# SalidasDigitales.net
KiCad netlist of a schematic drawn in Altium Designer
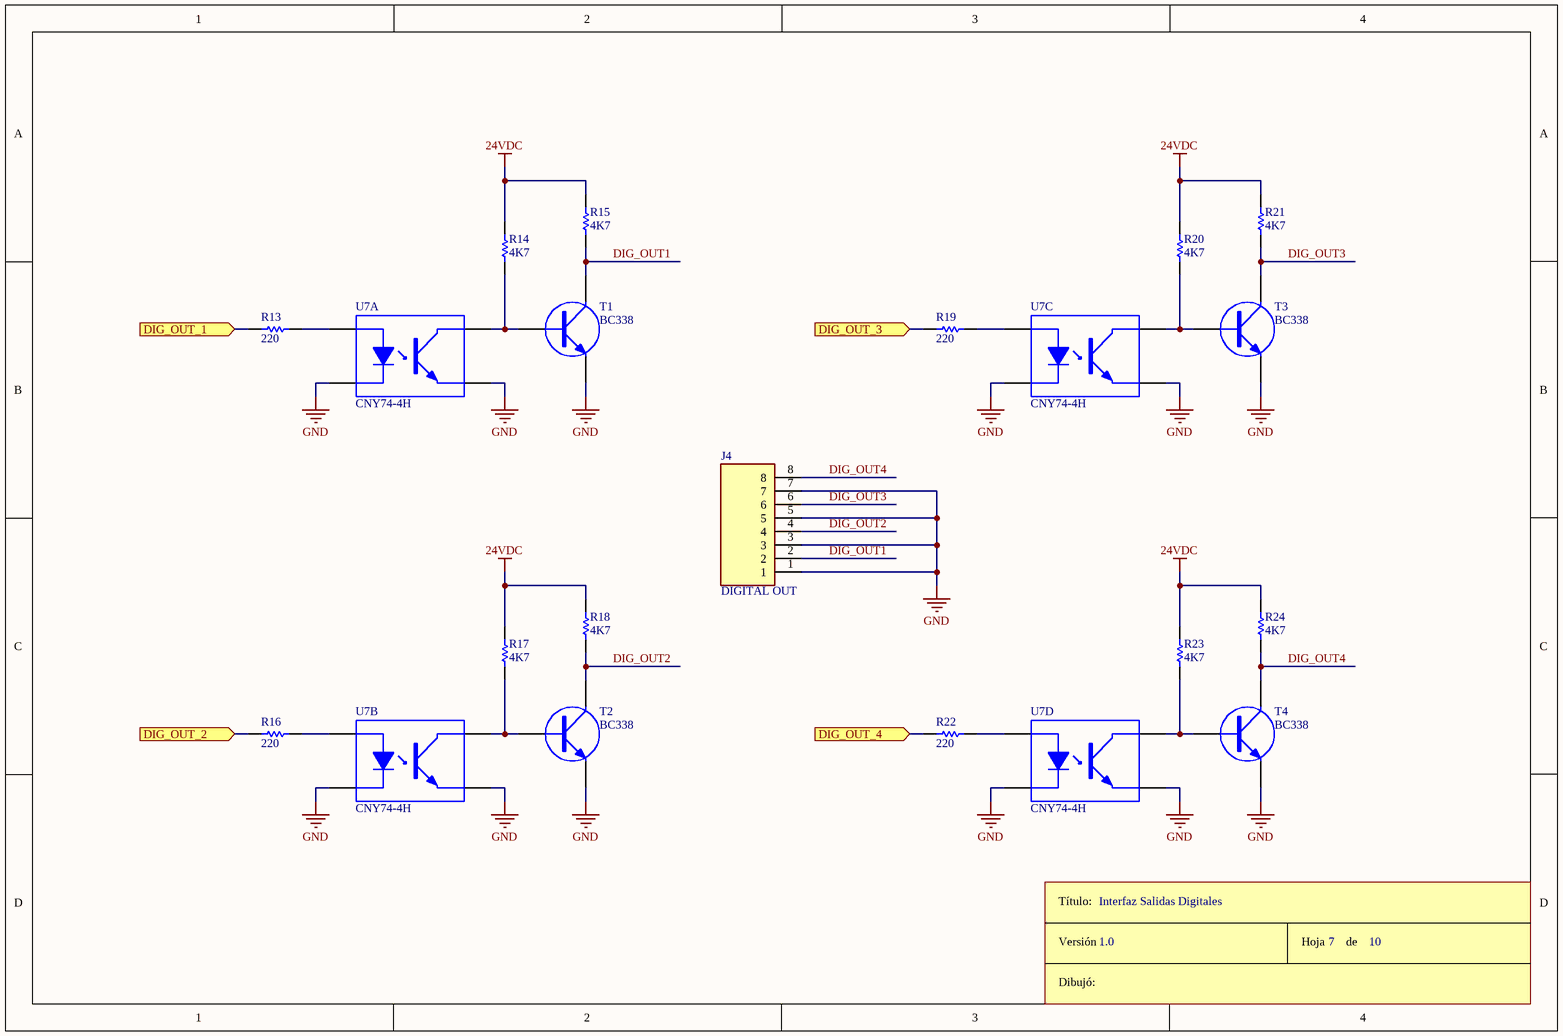
[diagram p0: SalidasDigitales.SchDoc]

(export (version "E")
  (design (tool "Eeschema 10.0.6"))
  (components
    (comp (ref "J4")
      (value "DIGITAL OUT")
      (footprint "TE_1586863-8")
      (description "Conn Power HDR 8 POS 4.2mm Solder RA Thru-Hole 8 Terminal 1 Port Tray")
      (fields (field (name "MF") "TE Connectivity") (field (name "MP") "1586863-8"))
      (libsource (lib "MFW8R") (part "1586863-8"))
    )
    (comp (ref "R13") (value "220") (footprint "RES300") (libsource (lib "LIBEBAL") (part "RES")))
    (comp (ref "R14") (value "4K7") (footprint "RES400") (libsource (lib "LIBEBAL") (part "RES")))
    (comp (ref "R15") (value "4K7") (footprint "RES400") (libsource (lib "LIBEBAL") (part "RES")))
    (comp (ref "R16") (value "220") (footprint "RES300") (libsource (lib "LIBEBAL") (part "RES")))
    (comp (ref "R17") (value "4K7") (footprint "RES400") (libsource (lib "LIBEBAL") (part "RES")))
    (comp (ref "R18") (value "4K7") (footprint "RES400") (libsource (lib "LIBEBAL") (part "RES")))
    (comp (ref "R19") (value "220") (footprint "RES300") (libsource (lib "LIBEBAL") (part "RES")))
    (comp (ref "R20") (value "4K7") (footprint "RES400") (libsource (lib "LIBEBAL") (part "RES")))
    (comp (ref "R21") (value "4K7") (footprint "RES400") (libsource (lib "LIBEBAL") (part "RES")))
    (comp (ref "R22") (value "220") (footprint "RES300") (libsource (lib "LIBEBAL") (part "RES")))
    (comp (ref "R23") (value "4K7") (footprint "RES400") (libsource (lib "LIBEBAL") (part "RES")))
    (comp (ref "R24") (value "4K7") (footprint "RES400") (libsource (lib "LIBEBAL") (part "RES")))
    (comp (ref "ROT6") (value "Rótulo") (libsource (lib "LIB PIO IX") (part "Rótulo")))
    (comp (ref "T1") (value "BC338") (footprint "TO92") (libsource (lib "LIBEBAL") (part "TRANSISTOR NPN")))
    (comp (ref "T2") (value "BC338") (footprint "TO92") (libsource (lib "LIBEBAL") (part "TRANSISTOR NPN")))
    (comp (ref "T3") (value "BC338") (footprint "TO92") (libsource (lib "LIBEBAL") (part "TRANSISTOR NPN")))
    (comp (ref "T4") (value "BC338") (footprint "TO92") (libsource (lib "LIBEBAL") (part "TRANSISTOR NPN")))
    (comp (ref "U7") (value "CNY74-4H") (footprint "DIP16") (libsource (lib "LIBEBAL") (part "CNY74-4H")))
  )
  (nets
    (net (code "1") (name "/DIG_OUT1") (class "Default")
      (node (ref "J4") (pin "2") (pinfunction "2_2") (pintype "passive"))
      (node (ref "R15") (pin "1") (pinfunction "1_1") (pintype "passive"))
      (node (ref "T1") (pin "2") (pinfunction "C_2") (pintype "passive"))
    )
    (net (code "2") (name "/DIG_OUT2") (class "Default")
      (node (ref "J4") (pin "4") (pinfunction "4_4") (pintype "passive"))
      (node (ref "R18") (pin "1") (pinfunction "1_1") (pintype "passive"))
      (node (ref "T2") (pin "2") (pinfunction "C_2") (pintype "passive"))
    )
    (net (code "3") (name "/DIG_OUT3") (class "Default")
      (node (ref "J4") (pin "6") (pinfunction "6_6") (pintype "passive"))
      (node (ref "R21") (pin "1") (pinfunction "1_1") (pintype "passive"))
      (node (ref "T3") (pin "2") (pinfunction "C_2") (pintype "passive"))
    )
    (net (code "4") (name "/DIG_OUT4") (class "Default")
      (node (ref "J4") (pin "8") (pinfunction "8_8") (pintype "passive"))
      (node (ref "R24") (pin "1") (pinfunction "1_1") (pintype "passive"))
      (node (ref "T4") (pin "2") (pinfunction "C_2") (pintype "passive"))
    )
    (net (code "5") (name "/DIG_OUT_1") (class "Default")
      (node (ref "R13") (pin "1") (pinfunction "1_1") (pintype "passive"))
    )
    (net (code "6") (name "/DIG_OUT_2") (class "Default")
      (node (ref "R16") (pin "1") (pinfunction "1_1") (pintype "passive"))
    )
    (net (code "7") (name "/DIG_OUT_3") (class "Default")
      (node (ref "R19") (pin "1") (pinfunction "1_1") (pintype "passive"))
    )
    (net (code "8") (name "/DIG_OUT_4") (class "Default")
      (node (ref "R22") (pin "1") (pinfunction "1_1") (pintype "passive"))
    )
    (net (code "9") (name "24VDC") (class "Default")
      (node (ref "R14") (pin "2") (pinfunction "2_2") (pintype "passive"))
      (node (ref "R15") (pin "2") (pinfunction "2_2") (pintype "passive"))
      (node (ref "R17") (pin "2") (pinfunction "2_2") (pintype "passive"))
      (node (ref "R18") (pin "2") (pinfunction "2_2") (pintype "passive"))
      (node (ref "R20") (pin "2") (pinfunction "2_2") (pintype "passive"))
      (node (ref "R21") (pin "2") (pinfunction "2_2") (pintype "passive"))
      (node (ref "R23") (pin "2") (pinfunction "2_2") (pintype "passive"))
      (node (ref "R24") (pin "2") (pinfunction "2_2") (pintype "passive"))
    )
    (net (code "10") (name "GND") (class "Default")
      (node (ref "J4") (pin "1") (pinfunction "1_1") (pintype "passive"))
      (node (ref "J4") (pin "3") (pinfunction "3_3") (pintype "passive"))
      (node (ref "J4") (pin "5") (pinfunction "5_5") (pintype "passive"))
      (node (ref "J4") (pin "7") (pinfunction "7_7") (pintype "passive"))
      (node (ref "T1") (pin "3") (pinfunction "E_3") (pintype "passive"))
      (node (ref "T2") (pin "3") (pinfunction "E_3") (pintype "passive"))
      (node (ref "T3") (pin "3") (pinfunction "E_3") (pintype "passive"))
      (node (ref "T4") (pin "3") (pinfunction "E_3") (pintype "passive"))
      (node (ref "U7") (pin "12") (pinfunction "E_12") (pintype "passive"))
      (node (ref "U7") (pin "13") (pinfunction "E_13") (pintype "passive"))
      (node (ref "U7") (pin "16") (pinfunction "E_16") (pintype "passive"))
      (node (ref "U7") (pin "2") (pinfunction "K_2") (pintype "passive"))
      (node (ref "U7") (pin "3") (pinfunction "K_3") (pintype "passive"))
      (node (ref "U7") (pin "6") (pinfunction "K_6") (pintype "passive"))
      (node (ref "U7") (pin "7") (pinfunction "K_7") (pintype "passive"))
      (node (ref "U7") (pin "9") (pinfunction "E_9") (pintype "passive"))
    )
    (net (code "11") (name "Net-(T1-B)") (class "Default")
      (node (ref "R14") (pin "1") (pinfunction "1_1") (pintype "passive"))
      (node (ref "T1") (pin "1") (pinfunction "B_1") (pintype "passive"))
      (node (ref "U7") (pin "15") (pinfunction "C_15") (pintype "passive"))
    )
    (net (code "12") (name "Net-(T2-B)") (class "Default")
      (node (ref "R17") (pin "1") (pinfunction "1_1") (pintype "passive"))
      (node (ref "T2") (pin "1") (pinfunction "B_1") (pintype "passive"))
      (node (ref "U7") (pin "14") (pinfunction "C_14") (pintype "passive"))
    )
    (net (code "13") (name "Net-(T3-B)") (class "Default")
      (node (ref "R20") (pin "1") (pinfunction "1_1") (pintype "passive"))
      (node (ref "T3") (pin "1") (pinfunction "B_1") (pintype "passive"))
      (node (ref "U7") (pin "11") (pinfunction "C_11") (pintype "passive"))
    )
    (net (code "14") (name "Net-(T4-B)") (class "Default")
      (node (ref "R23") (pin "1") (pinfunction "1_1") (pintype "passive"))
      (node (ref "T4") (pin "1") (pinfunction "B_1") (pintype "passive"))
      (node (ref "U7") (pin "10") (pinfunction "C_10") (pintype "passive"))
    )
    (net (code "15") (name "Net-(U7A-A)") (class "Default")
      (node (ref "R13") (pin "2") (pinfunction "2_2") (pintype "passive"))
      (node (ref "U7") (pin "1") (pinfunction "A_1") (pintype "passive"))
    )
    (net (code "16") (name "Net-(U7B-A)") (class "Default")
      (node (ref "R16") (pin "2") (pinfunction "2_2") (pintype "passive"))
      (node (ref "U7") (pin "4") (pinfunction "A_4") (pintype "passive"))
    )
    (net (code "17") (name "Net-(U7C-A)") (class "Default")
      (node (ref "R19") (pin "2") (pinfunction "2_2") (pintype "passive"))
      (node (ref "U7") (pin "5") (pinfunction "A_5") (pintype "passive"))
    )
    (net (code "18") (name "Net-(U7D-A)") (class "Default")
      (node (ref "R22") (pin "2") (pinfunction "2_2") (pintype "passive"))
      (node (ref "U7") (pin "8") (pinfunction "A_8") (pintype "passive"))
    )
  )
)
